# ProProject___2024-06-06.net
KiCad netlist of a schematic drawn in EasyEDA Pro
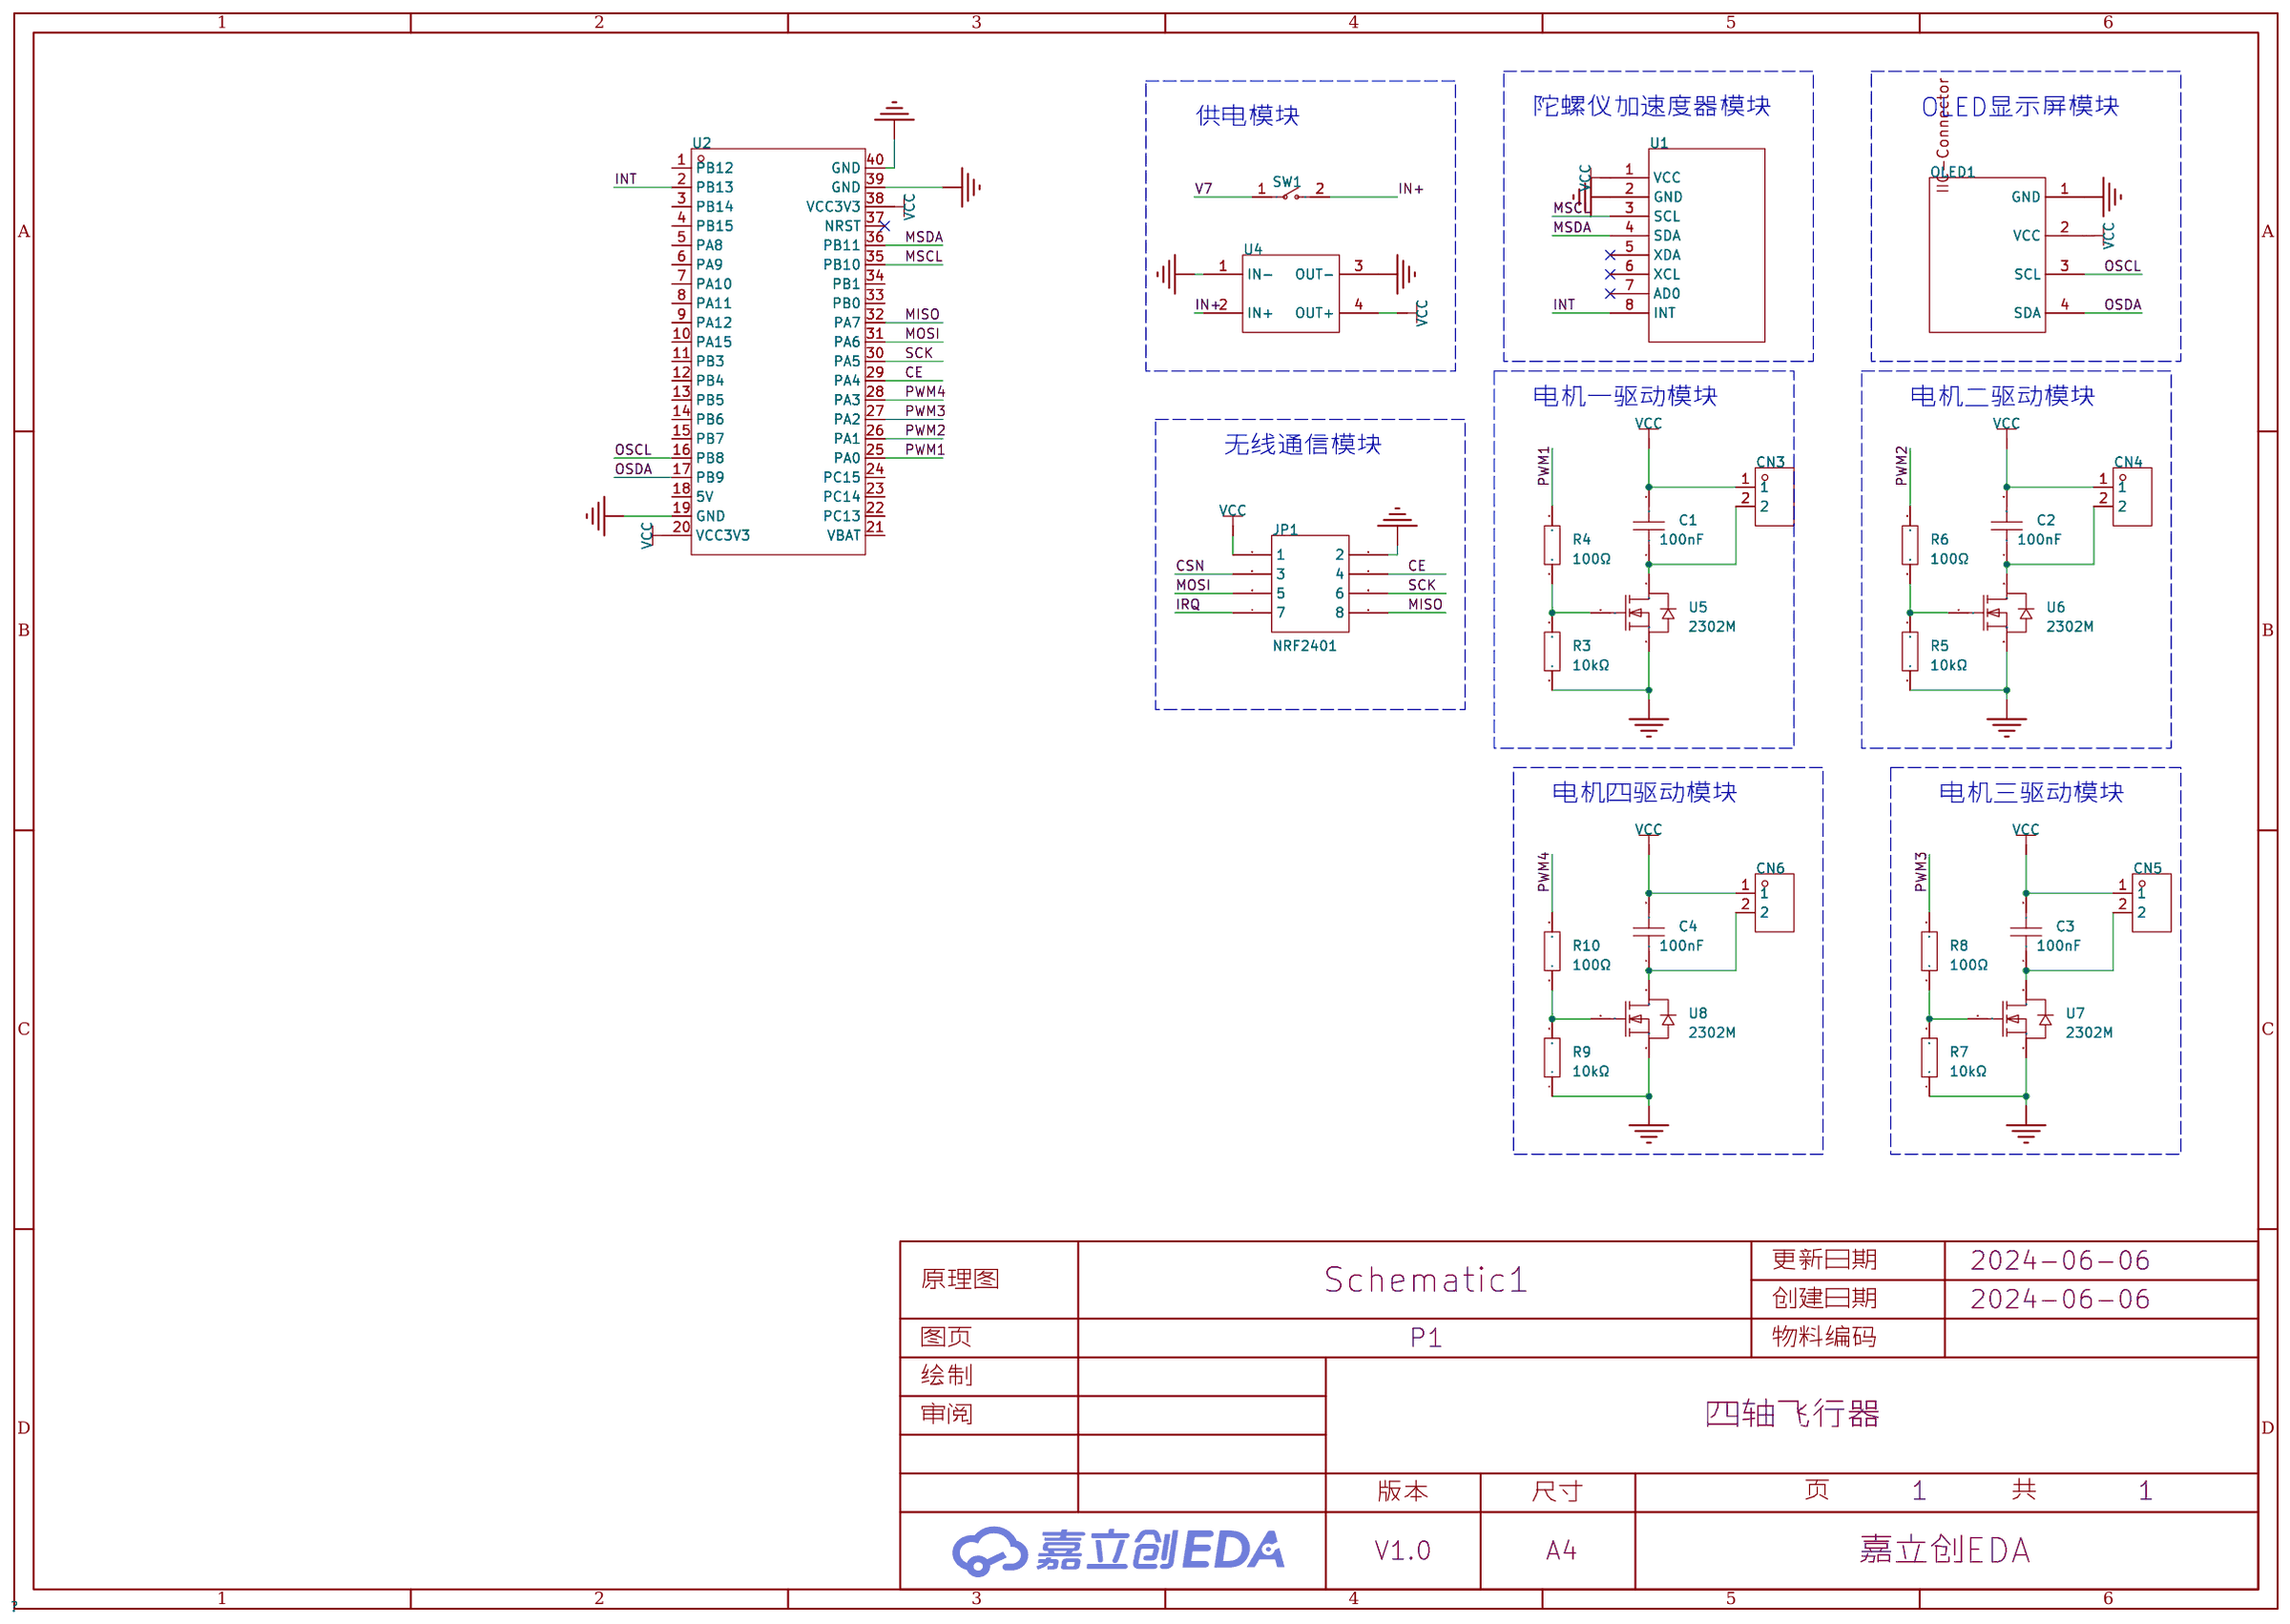
[diagram p0: schematic sheet]

(export (version "E")
  (design (tool "Eeschema 10.0.6"))
  (components
    (comp (ref "C1")
      (value "100nF")
      (footprint "easyedapro:C0603")
      (description "容值:100nF;精度:±10%;额定电压:50V;材质(温度系数):X7R;")
      (fields
        (field (name "Manufacturer Part") "CC0603KRX7R9BB104")
        (field (name "Manufacturer") "YAGEO(国巨)")
      )
      (libsource (lib "easyedapro") (part "CC0603KRX7R9BB104"))
    )
    (comp (ref "C2")
      (value "100nF")
      (footprint "easyedapro:C0603")
      (description "容值:100nF;精度:±10%;额定电压:50V;材质(温度系数):X7R;")
      (fields
        (field (name "Manufacturer Part") "CC0603KRX7R9BB104")
        (field (name "Manufacturer") "YAGEO(国巨)")
      )
      (libsource (lib "easyedapro") (part "CC0603KRX7R9BB104"))
    )
    (comp (ref "C3")
      (value "100nF")
      (footprint "easyedapro:C0603")
      (description "容值:100nF;精度:±10%;额定电压:50V;材质(温度系数):X7R;")
      (fields
        (field (name "Manufacturer Part") "CC0603KRX7R9BB104")
        (field (name "Manufacturer") "YAGEO(国巨)")
      )
      (libsource (lib "easyedapro") (part "CC0603KRX7R9BB104"))
    )
    (comp (ref "C4")
      (value "100nF")
      (footprint "easyedapro:C0603")
      (description "容值:100nF;精度:±10%;额定电压:50V;材质(温度系数):X7R;")
      (fields
        (field (name "Manufacturer Part") "CC0603KRX7R9BB104")
        (field (name "Manufacturer") "YAGEO(国巨)")
      )
      (libsource (lib "easyedapro") (part "CC0603KRX7R9BB104"))
    )
    (comp (ref "CN3")
      (value "ZX-XH2.54-2PZZ")
      (footprint "easyedapro:CONN-TH_2P-P2.50_HX25003-2A")
      (fields (field (name "Manufacturer") "Megastar(兆星)"))
      (libsource (lib "easyedapro") (part "ZX-XH2.54-2PZZ"))
    )
    (comp (ref "CN4")
      (value "ZX-XH2.54-2PZZ")
      (footprint "easyedapro:CONN-TH_2P-P2.50_HX25003-2A")
      (fields (field (name "Manufacturer") "Megastar(兆星)"))
      (libsource (lib "easyedapro") (part "ZX-XH2.54-2PZZ"))
    )
    (comp (ref "CN5")
      (value "ZX-XH2.54-2PZZ")
      (footprint "easyedapro:CONN-TH_2P-P2.50_HX25003-2A")
      (fields (field (name "Manufacturer") "Megastar(兆星)"))
      (libsource (lib "easyedapro") (part "ZX-XH2.54-2PZZ"))
    )
    (comp (ref "CN6")
      (value "ZX-XH2.54-2PZZ")
      (footprint "easyedapro:CONN-TH_2P-P2.50_HX25003-2A")
      (fields (field (name "Manufacturer") "Megastar(兆星)"))
      (libsource (lib "easyedapro") (part "ZX-XH2.54-2PZZ"))
    )
    (comp (ref "JP1")
      (value "NRF2401")
      (footprint "easyedapro:IDE2X4")
      (libsource (lib "easyedapro") (part "NRF2401"))
    )
    (comp (ref "OLED1")
      (value "0.96OLED_4P_MODULE_JX")
      (footprint "easyedapro:0.96OLED_4P")
      (libsource (lib "easyedapro") (part "0.96OLED_4P_MODULE_JX"))
    )
    (comp (ref "R3")
      (value "10kΩ")
      (footprint "easyedapro:R0805")
      (description "电阻类型:厚膜电阻;阻值:10kΩ;精度:±1%;功率:125mW;最大工作电压:150V;温度系数:±100ppm/°C;")
      (fields
        (field (name "Manufacturer Part") "0805W8F1002T5E")
        (field (name "Manufacturer") "UNI-ROYAL(厚声)")
      )
      (libsource (lib "easyedapro") (part "0805W8F1002T5E"))
    )
    (comp (ref "R4")
      (value "100Ω")
      (footprint "easyedapro:R0805")
      (description "电阻类型:厚膜电阻;阻值:100Ω;精度:±1%;功率:125mW;最大工作电压:150V;温度系数:±100ppm/°C;")
      (fields
        (field (name "Manufacturer Part") "0805W8F1000T5E")
        (field (name "Manufacturer") "UNI-ROYAL(厚声)")
      )
      (libsource (lib "easyedapro") (part "0805W8F1000T5E"))
    )
    (comp (ref "R5")
      (value "10kΩ")
      (footprint "easyedapro:R0805")
      (description "电阻类型:厚膜电阻;阻值:10kΩ;精度:±1%;功率:125mW;最大工作电压:150V;温度系数:±100ppm/°C;")
      (fields
        (field (name "Manufacturer Part") "0805W8F1002T5E")
        (field (name "Manufacturer") "UNI-ROYAL(厚声)")
      )
      (libsource (lib "easyedapro") (part "0805W8F1002T5E"))
    )
    (comp (ref "R6")
      (value "100Ω")
      (footprint "easyedapro:R0805")
      (description "电阻类型:厚膜电阻;阻值:100Ω;精度:±1%;功率:125mW;最大工作电压:150V;温度系数:±100ppm/°C;")
      (fields
        (field (name "Manufacturer Part") "0805W8F1000T5E")
        (field (name "Manufacturer") "UNI-ROYAL(厚声)")
      )
      (libsource (lib "easyedapro") (part "0805W8F1000T5E"))
    )
    (comp (ref "R7")
      (value "10kΩ")
      (footprint "easyedapro:R0805")
      (description "电阻类型:厚膜电阻;阻值:10kΩ;精度:±1%;功率:125mW;最大工作电压:150V;温度系数:±100ppm/°C;")
      (fields
        (field (name "Manufacturer Part") "0805W8F1002T5E")
        (field (name "Manufacturer") "UNI-ROYAL(厚声)")
      )
      (libsource (lib "easyedapro") (part "0805W8F1002T5E"))
    )
    (comp (ref "R8")
      (value "100Ω")
      (footprint "easyedapro:R0805")
      (description "电阻类型:厚膜电阻;阻值:100Ω;精度:±1%;功率:125mW;最大工作电压:150V;温度系数:±100ppm/°C;")
      (fields
        (field (name "Manufacturer Part") "0805W8F1000T5E")
        (field (name "Manufacturer") "UNI-ROYAL(厚声)")
      )
      (libsource (lib "easyedapro") (part "0805W8F1000T5E"))
    )
    (comp (ref "R9")
      (value "10kΩ")
      (footprint "easyedapro:R0805")
      (description "电阻类型:厚膜电阻;阻值:10kΩ;精度:±1%;功率:125mW;最大工作电压:150V;温度系数:±100ppm/°C;")
      (fields
        (field (name "Manufacturer Part") "0805W8F1002T5E")
        (field (name "Manufacturer") "UNI-ROYAL(厚声)")
      )
      (libsource (lib "easyedapro") (part "0805W8F1002T5E"))
    )
    (comp (ref "R10")
      (value "100Ω")
      (footprint "easyedapro:R0805")
      (description "电阻类型:厚膜电阻;阻值:100Ω;精度:±1%;功率:125mW;最大工作电压:150V;温度系数:±100ppm/°C;")
      (fields
        (field (name "Manufacturer Part") "0805W8F1000T5E")
        (field (name "Manufacturer") "UNI-ROYAL(厚声)")
      )
      (libsource (lib "easyedapro") (part "0805W8F1000T5E"))
    )
    (comp (ref "SW1")
      (value "KCD11-2P-R")
      (footprint "easyedapro:SW-TH_2P-L15.0-W10.5-P5.00_KCD11-2P-R")
      (description "带灯:无;引脚样式:焊片;额定电流:3A;额定电压(AC):250V;额定电压(DC):-;电路结构:单刀单掷;机械寿命:1万次;")
      (fields (field (name "Manufacturer") "SHOU HAN(首韩)"))
      (libsource (lib "easyedapro") (part "KCD11-2P-R"))
    )
    (comp (ref "U1")
      (value "~")
      (footprint "easyedapro:Module-MPU6050")
      (libsource (lib "easyedapro") (part "MPU6050模块"))
    )
    (comp (ref "U2")
      (value "STM32F103C8T6-Card")
      (footprint "easyedapro:CONN-TH_L53.3-W22.9_STM32F103C8T6-CARD")
      (libsource (lib "easyedapro") (part "STM32F103C8T6-CARD"))
    )
    (comp (ref "U4")
      (value "~")
      (footprint "easyedapro:MP1548EN可调电源模块")
      (description "输入4.5-28V；输出0.8-20V，Max3A；尺寸22*17*4mm")
      (fields (field (name "Manufacturer") "淘宝zave旗舰店"))
      (libsource (lib "easyedapro") (part "MP1584EN可调电源降压模块"))
    )
    (comp (ref "U5")
      (value "2302M")
      (footprint "easyedapro:SOT-23-3_L2.9-W1.3-P0.95-LS2.4-BR")
      (fields (field (name "Manufacturer") "FM(富满)"))
      (libsource (lib "easyedapro") (part "2302M"))
    )
    (comp (ref "U6")
      (value "2302M")
      (footprint "easyedapro:SOT-23-3_L2.9-W1.3-P0.95-LS2.4-BR")
      (fields (field (name "Manufacturer") "FM(富满)"))
      (libsource (lib "easyedapro") (part "2302M"))
    )
    (comp (ref "U7")
      (value "2302M")
      (footprint "easyedapro:SOT-23-3_L2.9-W1.3-P0.95-LS2.4-BR")
      (fields (field (name "Manufacturer") "FM(富满)"))
      (libsource (lib "easyedapro") (part "2302M"))
    )
    (comp (ref "U8")
      (value "2302M")
      (footprint "easyedapro:SOT-23-3_L2.9-W1.3-P0.95-LS2.4-BR")
      (fields (field (name "Manufacturer") "FM(富满)"))
      (libsource (lib "easyedapro") (part "2302M"))
    )
  )
  (nets
    (net (code "1") (name "/CE") (class "Default")
      (node (ref "JP1") (pin "4") (pinfunction "4_4") (pintype "input"))
      (node (ref "U2") (pin "29") (pinfunction "PA4_29") (pintype "unspecified"))
    )
    (net (code "2") (name "/CSN") (class "Default")
      (node (ref "JP1") (pin "3") (pinfunction "3_3") (pintype "input"))
    )
    (net (code "3") (name "/IN+") (class "Default")
      (node (ref "SW1") (pin "2") (pinfunction "2_2") (pintype "unspecified"))
      (node (ref "U4") (pin "2") (pinfunction "IN+_2") (pintype "input"))
    )
    (net (code "4") (name "/INT") (class "Default")
      (node (ref "U1") (pin "8") (pinfunction "INT_8") (pintype "input"))
      (node (ref "U2") (pin "2") (pinfunction "PB13_2") (pintype "unspecified"))
    )
    (net (code "5") (name "/IRQ") (class "Default")
      (node (ref "JP1") (pin "7") (pinfunction "7_7") (pintype "input"))
    )
    (net (code "6") (name "/MISO") (class "Default")
      (node (ref "JP1") (pin "8") (pinfunction "8_8") (pintype "input"))
      (node (ref "U2") (pin "32") (pinfunction "PA7_32") (pintype "unspecified"))
    )
    (net (code "7") (name "/MOSI") (class "Default")
      (node (ref "JP1") (pin "5") (pinfunction "5_5") (pintype "input"))
      (node (ref "U2") (pin "31") (pinfunction "PA6_31") (pintype "unspecified"))
    )
    (net (code "8") (name "/MSCL") (class "Default")
      (node (ref "U1") (pin "3") (pinfunction "SCL_3") (pintype "input"))
      (node (ref "U2") (pin "35") (pinfunction "PB10_35") (pintype "unspecified"))
    )
    (net (code "9") (name "/MSDA") (class "Default")
      (node (ref "U1") (pin "4") (pinfunction "SDA_4") (pintype "input"))
      (node (ref "U2") (pin "36") (pinfunction "PB11_36") (pintype "unspecified"))
    )
    (net (code "10") (name "/OSCL") (class "Default")
      (node (ref "OLED1") (pin "3") (pinfunction "SCL_3") (pintype "unspecified"))
      (node (ref "U2") (pin "16") (pinfunction "PB8_16") (pintype "unspecified"))
    )
    (net (code "11") (name "/OSDA") (class "Default")
      (node (ref "OLED1") (pin "4") (pinfunction "SDA_4") (pintype "unspecified"))
      (node (ref "U2") (pin "17") (pinfunction "PB9_17") (pintype "unspecified"))
    )
    (net (code "12") (name "/PWM1") (class "Default")
      (node (ref "R4") (pin "2") (pinfunction "2_2") (pintype "input"))
      (node (ref "U2") (pin "25") (pinfunction "PA0_25") (pintype "unspecified"))
    )
    (net (code "13") (name "/PWM2") (class "Default")
      (node (ref "R6") (pin "2") (pinfunction "2_2") (pintype "input"))
      (node (ref "U2") (pin "26") (pinfunction "PA1_26") (pintype "unspecified"))
    )
    (net (code "14") (name "/PWM3") (class "Default")
      (node (ref "R8") (pin "2") (pinfunction "2_2") (pintype "input"))
      (node (ref "U2") (pin "27") (pinfunction "PA2_27") (pintype "unspecified"))
    )
    (net (code "15") (name "/PWM4") (class "Default")
      (node (ref "R10") (pin "2") (pinfunction "2_2") (pintype "input"))
      (node (ref "U2") (pin "28") (pinfunction "PA3_28") (pintype "unspecified"))
    )
    (net (code "16") (name "/SCK") (class "Default")
      (node (ref "JP1") (pin "6") (pinfunction "6_6") (pintype "input"))
      (node (ref "U2") (pin "30") (pinfunction "PA5_30") (pintype "unspecified"))
    )
    (net (code "17") (name "/V7") (class "Default")
      (node (ref "SW1") (pin "1") (pinfunction "1_1") (pintype "unspecified"))
    )
    (net (code "18") (name "GND") (class "Default")
      (node (ref "JP1") (pin "2") (pinfunction "2_2") (pintype "input"))
      (node (ref "OLED1") (pin "1") (pinfunction "GND_1") (pintype "unspecified"))
      (node (ref "R3") (pin "1") (pinfunction "1_1") (pintype "input"))
      (node (ref "R5") (pin "1") (pinfunction "1_1") (pintype "input"))
      (node (ref "R7") (pin "1") (pinfunction "1_1") (pintype "input"))
      (node (ref "R9") (pin "1") (pinfunction "1_1") (pintype "input"))
      (node (ref "U1") (pin "2") (pinfunction "GND_2") (pintype "input"))
      (node (ref "U2") (pin "19") (pinfunction "GND_19") (pintype "unspecified"))
      (node (ref "U2") (pin "39") (pinfunction "GND_39") (pintype "unspecified"))
      (node (ref "U2") (pin "40") (pinfunction "GND_40") (pintype "unspecified"))
      (node (ref "U4") (pin "1") (pinfunction "IN-_1") (pintype "input"))
      (node (ref "U4") (pin "3") (pinfunction "OUT-_3") (pintype "input"))
      (node (ref "U5") (pin "2") (pinfunction "S_2") (pintype "unspecified"))
      (node (ref "U6") (pin "2") (pinfunction "S_2") (pintype "unspecified"))
      (node (ref "U7") (pin "2") (pinfunction "S_2") (pintype "unspecified"))
      (node (ref "U8") (pin "2") (pinfunction "S_2") (pintype "unspecified"))
    )
    (net (code "19") (name "Net-(U5-D)") (class "Default")
      (node (ref "C1") (pin "1") (pinfunction "1_1") (pintype "unspecified"))
      (node (ref "CN3") (pin "2") (pinfunction "2_2") (pintype "unspecified"))
      (node (ref "U5") (pin "3") (pinfunction "D_3") (pintype "unspecified"))
    )
    (net (code "20") (name "Net-(U5-G)") (class "Default")
      (node (ref "R3") (pin "2") (pinfunction "2_2") (pintype "input"))
      (node (ref "R4") (pin "1") (pinfunction "1_1") (pintype "input"))
      (node (ref "U5") (pin "1") (pinfunction "G_1") (pintype "unspecified"))
    )
    (net (code "21") (name "Net-(U6-D)") (class "Default")
      (node (ref "C2") (pin "1") (pinfunction "1_1") (pintype "unspecified"))
      (node (ref "CN4") (pin "2") (pinfunction "2_2") (pintype "unspecified"))
      (node (ref "U6") (pin "3") (pinfunction "D_3") (pintype "unspecified"))
    )
    (net (code "22") (name "Net-(U6-G)") (class "Default")
      (node (ref "R5") (pin "2") (pinfunction "2_2") (pintype "input"))
      (node (ref "R6") (pin "1") (pinfunction "1_1") (pintype "input"))
      (node (ref "U6") (pin "1") (pinfunction "G_1") (pintype "unspecified"))
    )
    (net (code "23") (name "Net-(U7-D)") (class "Default")
      (node (ref "C3") (pin "1") (pinfunction "1_1") (pintype "unspecified"))
      (node (ref "CN5") (pin "2") (pinfunction "2_2") (pintype "unspecified"))
      (node (ref "U7") (pin "3") (pinfunction "D_3") (pintype "unspecified"))
    )
    (net (code "24") (name "Net-(U7-G)") (class "Default")
      (node (ref "R7") (pin "2") (pinfunction "2_2") (pintype "input"))
      (node (ref "R8") (pin "1") (pinfunction "1_1") (pintype "input"))
      (node (ref "U7") (pin "1") (pinfunction "G_1") (pintype "unspecified"))
    )
    (net (code "25") (name "Net-(U8-D)") (class "Default")
      (node (ref "C4") (pin "1") (pinfunction "1_1") (pintype "unspecified"))
      (node (ref "CN6") (pin "2") (pinfunction "2_2") (pintype "unspecified"))
      (node (ref "U8") (pin "3") (pinfunction "D_3") (pintype "unspecified"))
    )
    (net (code "26") (name "Net-(U8-G)") (class "Default")
      (node (ref "R10") (pin "1") (pinfunction "1_1") (pintype "input"))
      (node (ref "R9") (pin "2") (pinfunction "2_2") (pintype "input"))
      (node (ref "U8") (pin "1") (pinfunction "G_1") (pintype "unspecified"))
    )
    (net (code "27") (name "VCC") (class "Default")
      (node (ref "C1") (pin "2") (pinfunction "2_2") (pintype "unspecified"))
      (node (ref "C2") (pin "2") (pinfunction "2_2") (pintype "unspecified"))
      (node (ref "C3") (pin "2") (pinfunction "2_2") (pintype "unspecified"))
      (node (ref "C4") (pin "2") (pinfunction "2_2") (pintype "unspecified"))
      (node (ref "CN3") (pin "1") (pinfunction "1_1") (pintype "unspecified"))
      (node (ref "CN4") (pin "1") (pinfunction "1_1") (pintype "unspecified"))
      (node (ref "CN5") (pin "1") (pinfunction "1_1") (pintype "unspecified"))
      (node (ref "CN6") (pin "1") (pinfunction "1_1") (pintype "unspecified"))
      (node (ref "JP1") (pin "1") (pinfunction "1_1") (pintype "input"))
      (node (ref "OLED1") (pin "2") (pinfunction "VCC_2") (pintype "unspecified"))
      (node (ref "U1") (pin "1") (pinfunction "VCC_1") (pintype "input"))
      (node (ref "U2") (pin "20") (pinfunction "VCC3V3_20") (pintype "unspecified"))
      (node (ref "U2") (pin "38") (pinfunction "VCC3V3_38") (pintype "unspecified"))
      (node (ref "U4") (pin "4") (pinfunction "OUT+_4") (pintype "input"))
    )
    (net (code "28") (name "unconnected-(U1-AD0-Pad7)") (class "Default")
      (node (ref "U1") (pin "7") (pinfunction "AD0_7") (pintype "input+no_connect"))
    )
    (net (code "29") (name "unconnected-(U1-XCL-Pad6)") (class "Default")
      (node (ref "U1") (pin "6") (pinfunction "XCL_6") (pintype "input+no_connect"))
    )
    (net (code "30") (name "unconnected-(U1-XDA-Pad5)") (class "Default")
      (node (ref "U1") (pin "5") (pinfunction "XDA_5") (pintype "input+no_connect"))
    )
    (net (code "31") (name "unconnected-(U2-5V-Pad18)") (class "Default")
      (node (ref "U2") (pin "18") (pinfunction "5V_18") (pintype "unspecified"))
    )
    (net (code "32") (name "unconnected-(U2-NRST-Pad37)") (class "Default")
      (node (ref "U2") (pin "37") (pinfunction "NRST_37") (pintype "unspecified+no_connect"))
    )
    (net (code "33") (name "unconnected-(U2-PA8-Pad5)") (class "Default")
      (node (ref "U2") (pin "5") (pinfunction "PA8_5") (pintype "unspecified"))
    )
    (net (code "34") (name "unconnected-(U2-PA9-Pad6)") (class "Default")
      (node (ref "U2") (pin "6") (pinfunction "PA9_6") (pintype "unspecified"))
    )
    (net (code "35") (name "unconnected-(U2-PA10-Pad7)") (class "Default")
      (node (ref "U2") (pin "7") (pinfunction "PA10_7") (pintype "unspecified"))
    )
    (net (code "36") (name "unconnected-(U2-PA11-Pad8)") (class "Default")
      (node (ref "U2") (pin "8") (pinfunction "PA11_8") (pintype "unspecified"))
    )
    (net (code "37") (name "unconnected-(U2-PA12-Pad9)") (class "Default")
      (node (ref "U2") (pin "9") (pinfunction "PA12_9") (pintype "unspecified"))
    )
    (net (code "38") (name "unconnected-(U2-PA15-Pad10)") (class "Default")
      (node (ref "U2") (pin "10") (pinfunction "PA15_10") (pintype "unspecified"))
    )
    (net (code "39") (name "unconnected-(U2-PB0-Pad33)") (class "Default")
      (node (ref "U2") (pin "33") (pinfunction "PB0_33") (pintype "unspecified"))
    )
    (net (code "40") (name "unconnected-(U2-PB1-Pad34)") (class "Default")
      (node (ref "U2") (pin "34") (pinfunction "PB1_34") (pintype "unspecified"))
    )
    (net (code "41") (name "unconnected-(U2-PB3-Pad11)") (class "Default")
      (node (ref "U2") (pin "11") (pinfunction "PB3_11") (pintype "unspecified"))
    )
    (net (code "42") (name "unconnected-(U2-PB4-Pad12)") (class "Default")
      (node (ref "U2") (pin "12") (pinfunction "PB4_12") (pintype "unspecified"))
    )
    (net (code "43") (name "unconnected-(U2-PB5-Pad13)") (class "Default")
      (node (ref "U2") (pin "13") (pinfunction "PB5_13") (pintype "unspecified"))
    )
    (net (code "44") (name "unconnected-(U2-PB6-Pad14)") (class "Default")
      (node (ref "U2") (pin "14") (pinfunction "PB6_14") (pintype "unspecified"))
    )
    (net (code "45") (name "unconnected-(U2-PB7-Pad15)") (class "Default")
      (node (ref "U2") (pin "15") (pinfunction "PB7_15") (pintype "unspecified"))
    )
    (net (code "46") (name "unconnected-(U2-PB12-Pad1)") (class "Default")
      (node (ref "U2") (pin "1") (pinfunction "PB12_1") (pintype "unspecified"))
    )
    (net (code "47") (name "unconnected-(U2-PB14-Pad3)") (class "Default")
      (node (ref "U2") (pin "3") (pinfunction "PB14_3") (pintype "unspecified"))
    )
    (net (code "48") (name "unconnected-(U2-PB15-Pad4)") (class "Default")
      (node (ref "U2") (pin "4") (pinfunction "PB15_4") (pintype "unspecified"))
    )
    (net (code "49") (name "unconnected-(U2-PC13-Pad22)") (class "Default")
      (node (ref "U2") (pin "22") (pinfunction "PC13_22") (pintype "unspecified"))
    )
    (net (code "50") (name "unconnected-(U2-PC14-Pad23)") (class "Default")
      (node (ref "U2") (pin "23") (pinfunction "PC14_23") (pintype "unspecified"))
    )
    (net (code "51") (name "unconnected-(U2-PC15-Pad24)") (class "Default")
      (node (ref "U2") (pin "24") (pinfunction "PC15_24") (pintype "unspecified"))
    )
    (net (code "52") (name "unconnected-(U2-VBAT-Pad21)") (class "Default")
      (node (ref "U2") (pin "21") (pinfunction "VBAT_21") (pintype "unspecified"))
    )
  )
)
